# Attiny_bot.net
KiCad netlist of a schematic drawn in EAGLE
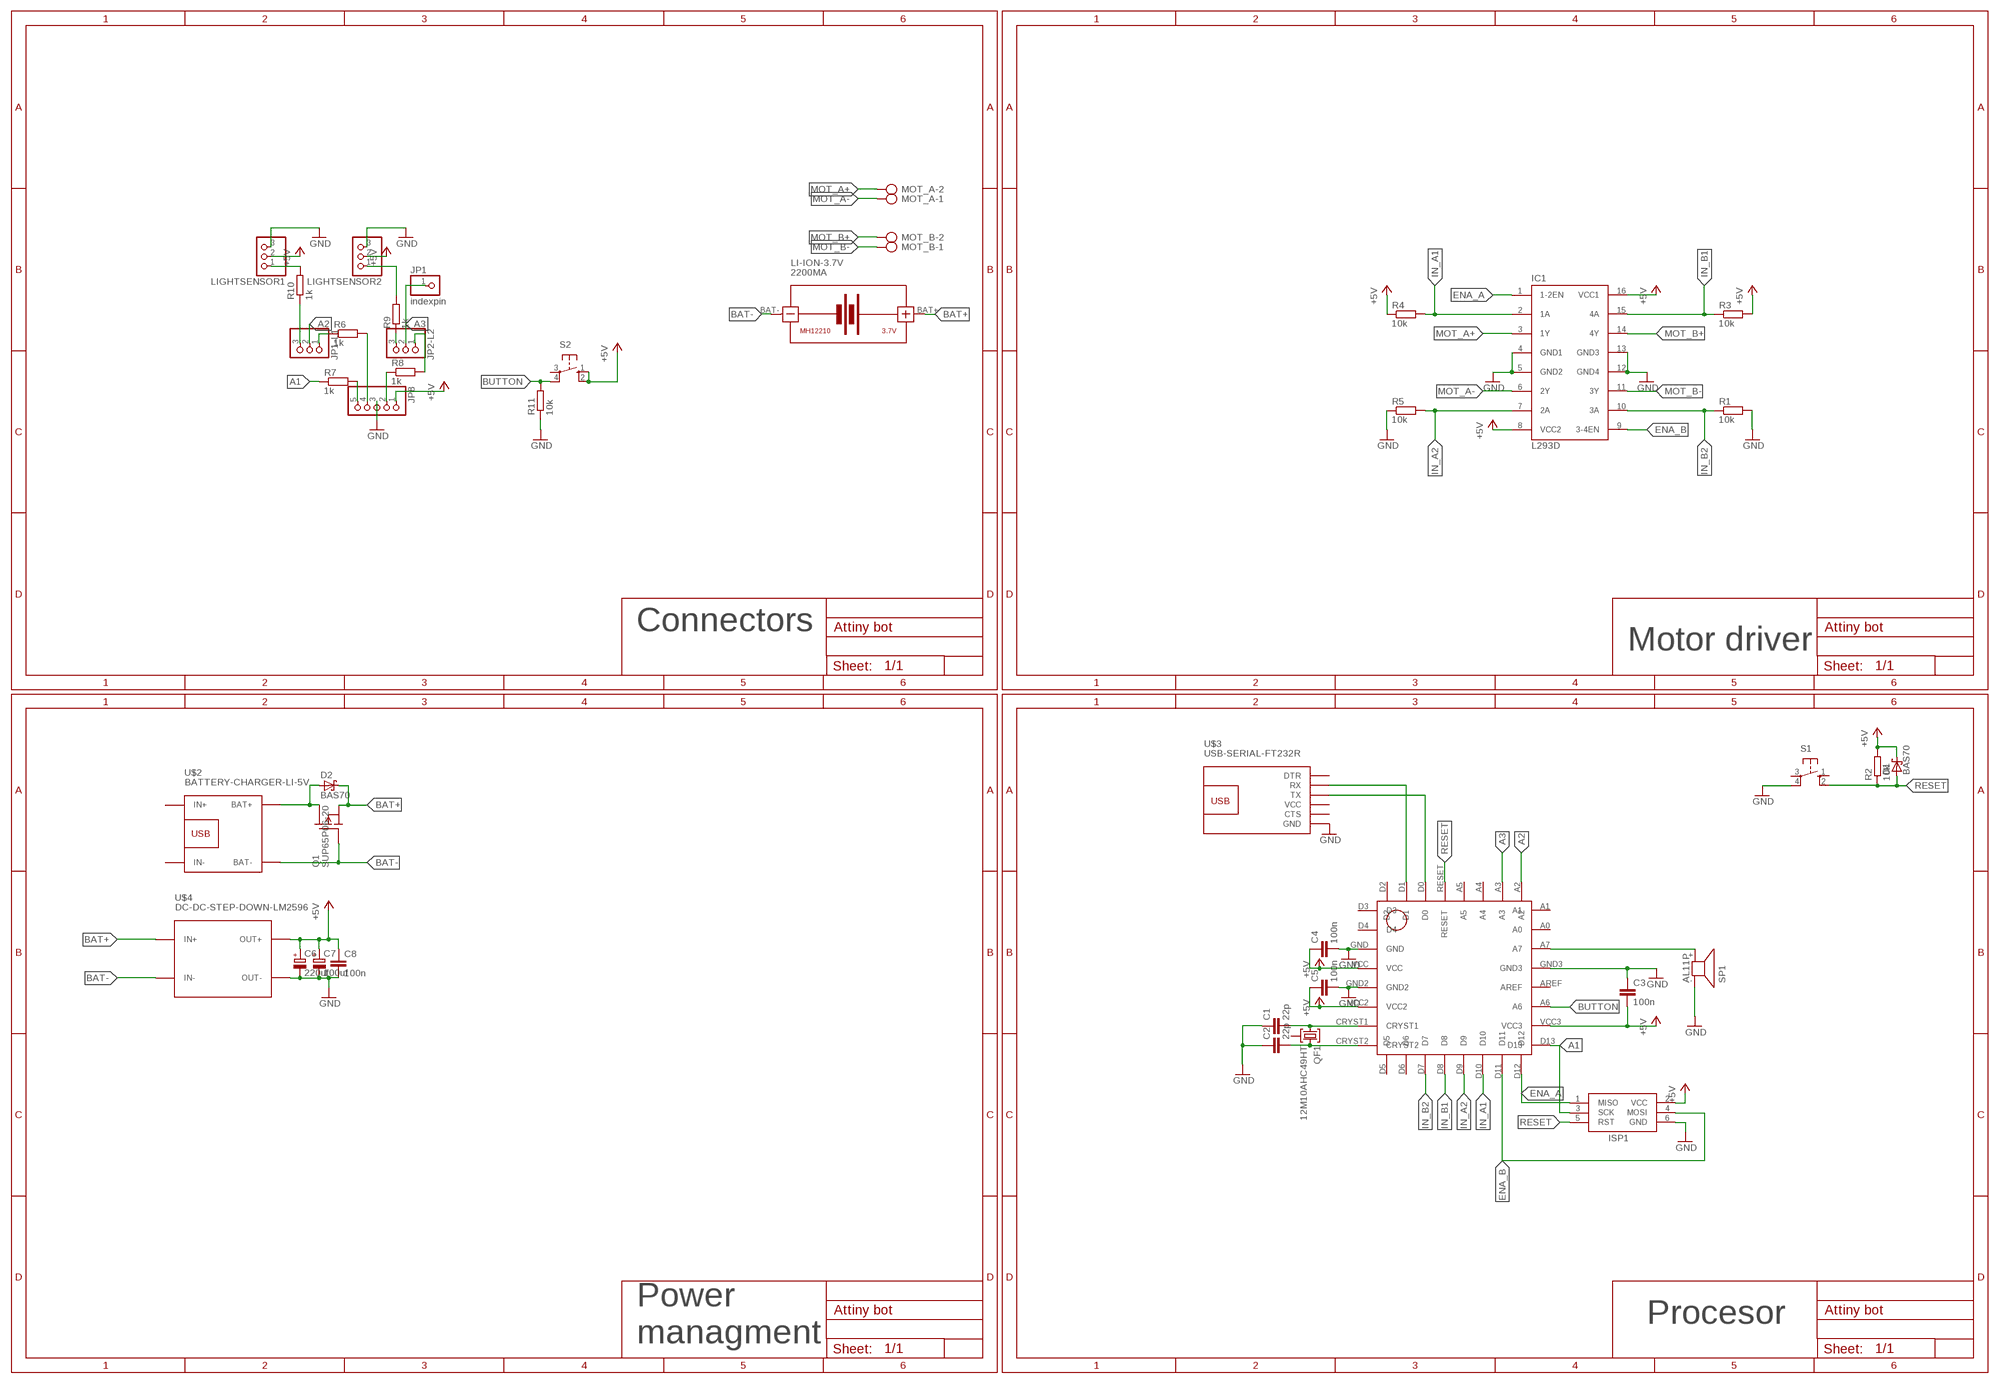
[diagram p0: schematic, sheet 1]

(export (version "E")
  (design (tool "Eeschema 10.0.6"))
  (components
    (comp (ref "C1")
      (value "22p")
      (footprint "eagle-import:C1206")
      (libsource (lib "eagle-import") (part "C-EUC1206"))
    )
    (comp (ref "C2")
      (value "22p")
      (footprint "eagle-import:C1206")
      (libsource (lib "eagle-import") (part "C-EUC1206"))
    )
    (comp (ref "C3")
      (value "100n")
      (footprint "eagle-import:C1206")
      (libsource (lib "eagle-import") (part "C-EUC1206"))
    )
    (comp (ref "C4")
      (value "100n")
      (footprint "eagle-import:C1206")
      (libsource (lib "eagle-import") (part "C-EUC1206"))
    )
    (comp (ref "C5")
      (value "100n")
      (footprint "eagle-import:C1206")
      (libsource (lib "eagle-import") (part "C-EUC1206"))
    )
    (comp (ref "C6")
      (value "220uf")
      (footprint "eagle-import:E3,5-8")
      (libsource (lib "eagle-import") (part "CPOL-EUE3.5-8"))
    )
    (comp (ref "C7")
      (value "100uf")
      (footprint "eagle-import:E3,5-8")
      (libsource (lib "eagle-import") (part "CPOL-EUE3.5-8"))
    )
    (comp (ref "C8")
      (value "100n")
      (footprint "eagle-import:C1206")
      (libsource (lib "eagle-import") (part "C-EUC1206"))
    )
    (comp (ref "D1")
      (value "BAS70")
      (footprint "eagle-import:SOT23")
      (libsource (lib "eagle-import") (part "BAS70"))
    )
    (comp (ref "D2")
      (value "BAS70")
      (footprint "eagle-import:SOT23")
      (libsource (lib "eagle-import") (part "BAS70"))
    )
    (comp (ref "IC1")
      (value "L293D")
      (footprint "eagle-import:DIL16")
      (libsource (lib "eagle-import") (part "L293D"))
    )
    (comp (ref "ISP1")
      (value "AVRISP-6")
      (footprint "eagle-import:AVRISP")
      (libsource (lib "eagle-import") (part "AVRISP-6"))
    )
    (comp (ref "JP1")
      (value "indexpin")
      (footprint "eagle-import:1X01")
      (libsource (lib "eagle-import") (part "PINHD-1X1"))
    )
    (comp (ref "JP1-L1")
      (value "PINHD-1X3")
      (footprint "eagle-import:1X03")
      (libsource (lib "eagle-import") (part "PINHD-1X3"))
    )
    (comp (ref "JP2-L2")
      (value "PINHD-1X3")
      (footprint "eagle-import:1X03")
      (libsource (lib "eagle-import") (part "PINHD-1X3"))
    )
    (comp (ref "JP8")
      (value "PINHD-1X5")
      (footprint "eagle-import:1X05")
      (libsource (lib "eagle-import") (part "PINHD-1X5"))
    )
    (comp (ref "LI-ION-3.7V")
      (value "2200MA")
      (footprint "eagle-import:BATTERY-LI-MH12210")
      (libsource (lib "eagle-import") (part "BATTERY-LI-MH12210"))
    )
    (comp (ref "LIGHTSENSOR1")
      (value "PINHD-1X3")
      (footprint "eagle-import:1X03")
      (libsource (lib "eagle-import") (part "PINHD-1X3"))
    )
    (comp (ref "LIGHTSENSOR2")
      (value "PINHD-1X3")
      (footprint "eagle-import:1X03")
      (libsource (lib "eagle-import") (part "PINHD-1X3"))
    )
    (comp (ref "MOT_A")
      (value "AK500/2")
      (footprint "eagle-import:AK500_2")
      (libsource (lib "eagle-import") (part "AK500/2"))
    )
    (comp (ref "MOT_B")
      (value "AK500/2")
      (footprint "eagle-import:AK500_2")
      (libsource (lib "eagle-import") (part "AK500/2"))
    )
    (comp (ref "Q1")
      (value "SUP65P06-20")
      (footprint "eagle-import:TO220")
      (libsource (lib "eagle-import") (part "SUP65P06-20"))
    )
    (comp (ref "QF1")
      (value "12M10AHC49HT")
      (footprint "eagle-import:HC49U")
      (libsource (lib "eagle-import") (part "12M10AHC49HT"))
    )
    (comp (ref "R1")
      (value "10k")
      (footprint "eagle-import:R1206")
      (libsource (lib "eagle-import") (part "R-EU_R1206"))
    )
    (comp (ref "R2")
      (value "10k")
      (footprint "eagle-import:R1206")
      (libsource (lib "eagle-import") (part "R-EU_R1206"))
    )
    (comp (ref "R3")
      (value "10k")
      (footprint "eagle-import:R1206")
      (libsource (lib "eagle-import") (part "R-EU_R1206"))
    )
    (comp (ref "R4")
      (value "10k")
      (footprint "eagle-import:R1206")
      (libsource (lib "eagle-import") (part "R-EU_R1206"))
    )
    (comp (ref "R5")
      (value "10k")
      (footprint "eagle-import:R1206")
      (libsource (lib "eagle-import") (part "R-EU_R1206"))
    )
    (comp (ref "R6")
      (value "1k")
      (footprint "eagle-import:R1206")
      (libsource (lib "eagle-import") (part "R-EU_R1206"))
    )
    (comp (ref "R7")
      (value "1k")
      (footprint "eagle-import:R1206")
      (libsource (lib "eagle-import") (part "R-EU_R1206"))
    )
    (comp (ref "R8")
      (value "1k")
      (footprint "eagle-import:R1206")
      (libsource (lib "eagle-import") (part "R-EU_R1206"))
    )
    (comp (ref "R9")
      (value "1k")
      (footprint "eagle-import:R1206")
      (libsource (lib "eagle-import") (part "R-EU_R1206"))
    )
    (comp (ref "R10")
      (value "1k")
      (footprint "eagle-import:R1206")
      (libsource (lib "eagle-import") (part "R-EU_R1206"))
    )
    (comp (ref "R11")
      (value "10k")
      (footprint "eagle-import:R1206")
      (libsource (lib "eagle-import") (part "R-EU_R1206"))
    )
    (comp (ref "S1")
      (value "10-XX")
      (footprint "eagle-import:B3F-10XX")
      (fields (field (name "MPN") "B3F-1000"))
      (libsource (lib "eagle-import") (part "10-XX"))
    )
    (comp (ref "S2")
      (value "10-XX")
      (footprint "eagle-import:B3F-10XX")
      (fields (field (name "MPN") "B3F-1000"))
      (libsource (lib "eagle-import") (part "10-XX"))
    )
    (comp (ref "SP1")
      (value "AL11P")
      (footprint "eagle-import:AL11P")
      (libsource (lib "eagle-import") (part "AL11P"))
    )
    (comp (ref "U$1")
      (value "PROCESSOR")
      (footprint "eagle-import:PROCESOR")
      (libsource (lib "eagle-import") (part "PROCESSOR"))
    )
    (comp (ref "U$2")
      (value "BATTERY-CHARGER-LI-5V")
      (footprint "eagle-import:BATTERY-CHARGER-LI-5V")
      (libsource (lib "eagle-import") (part "BATTERY-CHARGER-LI-5V"))
    )
    (comp (ref "U$3")
      (value "USB-SERIAL-FT232R")
      (footprint "eagle-import:USB-SERIAL-FT232R")
      (libsource (lib "eagle-import") (part "USB-SERIAL-FT232R"))
    )
    (comp (ref "U$4")
      (value "DC-DC-STEP-DOWN-LM2596")
      (footprint "eagle-import:DC-DC-STEP-DOWN-LM2596")
      (libsource (lib "eagle-import") (part "DC-DC-STEP-DOWN-LM2596"))
    )
  )
  (nets
    (net (code "1") (name "+5V") (class "Default")
      (node (ref "C3") (pin "2") (pinfunction "2_2") (pintype "passive"))
      (node (ref "C4") (pin "1") (pinfunction "1_1") (pintype "passive"))
      (node (ref "C5") (pin "1") (pinfunction "1_1") (pintype "passive"))
      (node (ref "C6") (pin "+") (pinfunction "+_+") (pintype "passive"))
      (node (ref "C7") (pin "+") (pinfunction "+_+") (pintype "passive"))
      (node (ref "C8") (pin "1") (pinfunction "1_1") (pintype "passive"))
      (node (ref "D1") (pin "3") (pinfunction "C_3") (pintype "passive"))
      (node (ref "IC1") (pin "16") (pinfunction "VCC1_16") (pintype "power_in"))
      (node (ref "IC1") (pin "8") (pinfunction "VCC2_8") (pintype "power_in"))
      (node (ref "ISP1") (pin "2") (pinfunction "VCC_2") (pintype "power_in"))
      (node (ref "JP8") (pin "1") (pinfunction "1_1") (pintype "passive"))
      (node (ref "LIGHTSENSOR1") (pin "2") (pinfunction "2_2") (pintype "passive"))
      (node (ref "LIGHTSENSOR2") (pin "2") (pinfunction "2_2") (pintype "passive"))
      (node (ref "R2") (pin "2") (pinfunction "2_2") (pintype "passive"))
      (node (ref "R3") (pin "2") (pinfunction "2_2") (pintype "passive"))
      (node (ref "R4") (pin "1") (pinfunction "1_1") (pintype "passive"))
      (node (ref "S2") (pin "1") (pinfunction "S_1") (pintype "passive"))
      (node (ref "S2") (pin "2") (pinfunction "S1_2") (pintype "passive"))
      (node (ref "U$1") (pin "VCC") (pinfunction "VCC_VCC") (pintype "bidirectional"))
      (node (ref "U$1") (pin "VCC2") (pinfunction "VCC2_VCC2") (pintype "bidirectional"))
      (node (ref "U$1") (pin "VCC3") (pinfunction "VCC3_VCC3") (pintype "bidirectional"))
      (node (ref "U$4") (pin "OUT+") (pinfunction "OUT+_OUT+") (pintype "bidirectional"))
    )
    (net (code "2") (name "/VCC") (class "Default")
      (node (ref "U$3") (pin "4") (pinfunction "VCC_4") (pintype "power_in"))
    )
    (net (code "3") (name "A1") (class "Default")
      (node (ref "ISP1") (pin "3") (pinfunction "SCK_3") (pintype "output"))
      (node (ref "R7") (pin "1") (pinfunction "1_1") (pintype "passive"))
      (node (ref "U$1") (pin "D13") (pinfunction "D13_D13") (pintype "bidirectional"))
    )
    (net (code "4") (name "A2") (class "Default")
      (node (ref "JP1-L1") (pin "2") (pinfunction "2_2") (pintype "passive"))
      (node (ref "U$1") (pin "A2") (pinfunction "A2_A2") (pintype "bidirectional"))
    )
    (net (code "5") (name "A3") (class "Default")
      (node (ref "JP1") (pin "1") (pinfunction "1_1") (pintype "passive"))
      (node (ref "JP2-L2") (pin "2") (pinfunction "2_2") (pintype "passive"))
      (node (ref "U$1") (pin "A3") (pinfunction "A3_A3") (pintype "bidirectional"))
    )
    (net (code "6") (name "BAT+") (class "Default")
      (node (ref "D2") (pin "3") (pinfunction "C_3") (pintype "passive"))
      (node (ref "LI-ION-3.7V") (pin "BAT+") (pinfunction "BAT+_BAT+") (pintype "power_in"))
      (node (ref "Q1") (pin "3") (pinfunction "S_3") (pintype "passive"))
      (node (ref "U$4") (pin "IN+") (pinfunction "IN+_IN+") (pintype "bidirectional"))
    )
    (net (code "7") (name "BAT-") (class "Default")
      (node (ref "LI-ION-3.7V") (pin "BAT-") (pinfunction "BAT-_BAT-") (pintype "power_in"))
      (node (ref "Q1") (pin "1") (pinfunction "G_1") (pintype "passive"))
      (node (ref "U$2") (pin "BAT-") (pinfunction "BAT-_BAT-") (pintype "bidirectional"))
      (node (ref "U$4") (pin "IN-") (pinfunction "IN-_IN-") (pintype "bidirectional"))
    )
    (net (code "8") (name "BUTTON") (class "Default")
      (node (ref "R11") (pin "2") (pinfunction "2_2") (pintype "passive"))
      (node (ref "S2") (pin "4") (pinfunction "P1_4") (pintype "passive"))
      (node (ref "U$1") (pin "A6") (pinfunction "A6_A6") (pintype "bidirectional"))
    )
    (net (code "9") (name "ENA_A") (class "Default")
      (node (ref "IC1") (pin "1") (pinfunction "1-2EN_1") (pintype "input"))
      (node (ref "ISP1") (pin "1") (pinfunction "MISO_1") (pintype "input"))
      (node (ref "U$1") (pin "D12") (pinfunction "D12_D12") (pintype "bidirectional"))
    )
    (net (code "10") (name "ENA_B") (class "Default")
      (node (ref "IC1") (pin "9") (pinfunction "3-4EN_9") (pintype "input"))
      (node (ref "ISP1") (pin "4") (pinfunction "MOSI_4") (pintype "output"))
      (node (ref "U$1") (pin "D11") (pinfunction "D11_D11") (pintype "bidirectional"))
    )
    (net (code "11") (name "GND") (class "Default")
      (node (ref "C1") (pin "1") (pinfunction "1_1") (pintype "passive"))
      (node (ref "C2") (pin "1") (pinfunction "1_1") (pintype "passive"))
      (node (ref "C3") (pin "1") (pinfunction "1_1") (pintype "passive"))
      (node (ref "C4") (pin "2") (pinfunction "2_2") (pintype "passive"))
      (node (ref "C5") (pin "2") (pinfunction "2_2") (pintype "passive"))
      (node (ref "C6") (pin "-") (pinfunction "-_-") (pintype "passive"))
      (node (ref "C7") (pin "-") (pinfunction "-_-") (pintype "passive"))
      (node (ref "C8") (pin "2") (pinfunction "2_2") (pintype "passive"))
      (node (ref "IC1") (pin "12") (pinfunction "GND4_12") (pintype "power_in"))
      (node (ref "IC1") (pin "13") (pinfunction "GND3_13") (pintype "power_in"))
      (node (ref "IC1") (pin "4") (pinfunction "GND1_4") (pintype "power_in"))
      (node (ref "IC1") (pin "5") (pinfunction "GND2_5") (pintype "power_in"))
      (node (ref "ISP1") (pin "6") (pinfunction "GND_6") (pintype "power_in"))
      (node (ref "JP8") (pin "3") (pinfunction "3_3") (pintype "passive"))
      (node (ref "LIGHTSENSOR1") (pin "3") (pinfunction "3_3") (pintype "passive"))
      (node (ref "LIGHTSENSOR2") (pin "3") (pinfunction "3_3") (pintype "passive"))
      (node (ref "R1") (pin "2") (pinfunction "2_2") (pintype "passive"))
      (node (ref "R11") (pin "1") (pinfunction "1_1") (pintype "passive"))
      (node (ref "R5") (pin "1") (pinfunction "1_1") (pintype "passive"))
      (node (ref "S1") (pin "4") (pinfunction "P1_4") (pintype "passive"))
      (node (ref "SP1") (pin "-") (pinfunction "1_-") (pintype "passive"))
      (node (ref "U$1") (pin "GND") (pinfunction "GND_GND") (pintype "bidirectional"))
      (node (ref "U$1") (pin "GND2") (pinfunction "GND2_GND2") (pintype "bidirectional"))
      (node (ref "U$1") (pin "GND3") (pinfunction "GND3_GND3") (pintype "bidirectional"))
      (node (ref "U$3") (pin "6") (pinfunction "GND_6") (pintype "bidirectional"))
      (node (ref "U$4") (pin "OUT-") (pinfunction "OUT-_OUT-") (pintype "bidirectional"))
    )
    (net (code "12") (name "IN_A1") (class "Default")
      (node (ref "IC1") (pin "2") (pinfunction "1A_2") (pintype "input"))
      (node (ref "R4") (pin "2") (pinfunction "2_2") (pintype "passive"))
      (node (ref "U$1") (pin "D10") (pinfunction "D10_D10") (pintype "bidirectional"))
    )
    (net (code "13") (name "IN_A2") (class "Default")
      (node (ref "IC1") (pin "7") (pinfunction "2A_7") (pintype "input"))
      (node (ref "R5") (pin "2") (pinfunction "2_2") (pintype "passive"))
      (node (ref "U$1") (pin "D9") (pinfunction "D9_D9") (pintype "bidirectional"))
    )
    (net (code "14") (name "IN_B1") (class "Default")
      (node (ref "IC1") (pin "15") (pinfunction "4A_15") (pintype "input"))
      (node (ref "R3") (pin "1") (pinfunction "1_1") (pintype "passive"))
      (node (ref "U$1") (pin "D8") (pinfunction "D8_D8") (pintype "bidirectional"))
    )
    (net (code "15") (name "IN_B2") (class "Default")
      (node (ref "IC1") (pin "10") (pinfunction "3A_10") (pintype "input"))
      (node (ref "R1") (pin "1") (pinfunction "1_1") (pintype "passive"))
      (node (ref "U$1") (pin "D7") (pinfunction "D7_D7") (pintype "bidirectional"))
    )
    (net (code "16") (name "MOT_A+") (class "Default")
      (node (ref "IC1") (pin "3") (pinfunction "1Y_3") (pintype "output"))
      (node (ref "MOT_A") (pin "2") (pinfunction "KL_2") (pintype "passive"))
    )
    (net (code "17") (name "MOT_A-") (class "Default")
      (node (ref "IC1") (pin "6") (pinfunction "2Y_6") (pintype "output"))
      (node (ref "MOT_A") (pin "1") (pinfunction "KL_1") (pintype "passive"))
    )
    (net (code "18") (name "MOT_B+") (class "Default")
      (node (ref "IC1") (pin "14") (pinfunction "4Y_14") (pintype "output"))
      (node (ref "MOT_B") (pin "2") (pinfunction "KL_2") (pintype "passive"))
    )
    (net (code "19") (name "MOT_B-") (class "Default")
      (node (ref "IC1") (pin "11") (pinfunction "3Y_11") (pintype "output"))
      (node (ref "MOT_B") (pin "1") (pinfunction "KL_1") (pintype "passive"))
    )
    (net (code "20") (name "Net-(C1-Pad2)") (class "Default")
      (node (ref "C1") (pin "2") (pinfunction "2_2") (pintype "passive"))
      (node (ref "QF1") (pin "1") (pinfunction "1_1") (pintype "passive"))
      (node (ref "U$1") (pin "CRYST1") (pinfunction "CRYST1_CRYST1") (pintype "bidirectional"))
    )
    (net (code "21") (name "Net-(C2-Pad2)") (class "Default")
      (node (ref "C2") (pin "2") (pinfunction "2_2") (pintype "passive"))
      (node (ref "QF1") (pin "3") (pinfunction "3_3") (pintype "passive"))
      (node (ref "U$1") (pin "CRYST2") (pinfunction "CRYST2_CRYST2") (pintype "bidirectional"))
    )
    (net (code "22") (name "Net-(D2-A)") (class "Default")
      (node (ref "D2") (pin "1") (pinfunction "A_1") (pintype "passive"))
      (node (ref "Q1") (pin "2") (pinfunction "D_2") (pintype "passive"))
      (node (ref "U$2") (pin "BAT+") (pinfunction "BAT+_BAT+") (pintype "bidirectional"))
    )
    (net (code "23") (name "Net-(JP1-L1-Pad1)") (class "Default")
      (node (ref "JP1-L1") (pin "1") (pinfunction "1_1") (pintype "passive"))
      (node (ref "R6") (pin "1") (pinfunction "1_1") (pintype "passive"))
    )
    (net (code "24") (name "Net-(JP1-L1-Pad3)") (class "Default")
      (node (ref "JP1-L1") (pin "3") (pinfunction "3_3") (pintype "passive"))
      (node (ref "R10") (pin "1") (pinfunction "1_1") (pintype "passive"))
    )
    (net (code "25") (name "Net-(JP2-L2-Pad1)") (class "Default")
      (node (ref "JP2-L2") (pin "1") (pinfunction "1_1") (pintype "passive"))
      (node (ref "R8") (pin "2") (pinfunction "2_2") (pintype "passive"))
    )
    (net (code "26") (name "Net-(JP2-L2-Pad3)") (class "Default")
      (node (ref "JP2-L2") (pin "3") (pinfunction "3_3") (pintype "passive"))
      (node (ref "R9") (pin "1") (pinfunction "1_1") (pintype "passive"))
    )
    (net (code "27") (name "Net-(JP8-Pad2)") (class "Default")
      (node (ref "JP8") (pin "2") (pinfunction "2_2") (pintype "passive"))
      (node (ref "R8") (pin "1") (pinfunction "1_1") (pintype "passive"))
    )
    (net (code "28") (name "Net-(JP8-Pad4)") (class "Default")
      (node (ref "JP8") (pin "4") (pinfunction "4_4") (pintype "passive"))
      (node (ref "R6") (pin "2") (pinfunction "2_2") (pintype "passive"))
    )
    (net (code "29") (name "Net-(JP8-Pad5)") (class "Default")
      (node (ref "JP8") (pin "5") (pinfunction "5_5") (pintype "passive"))
      (node (ref "R7") (pin "2") (pinfunction "2_2") (pintype "passive"))
    )
    (net (code "30") (name "Net-(LIGHTSENSOR1-Pad1)") (class "Default")
      (node (ref "LIGHTSENSOR1") (pin "1") (pinfunction "1_1") (pintype "passive"))
      (node (ref "R10") (pin "2") (pinfunction "2_2") (pintype "passive"))
    )
    (net (code "31") (name "Net-(LIGHTSENSOR2-Pad1)") (class "Default")
      (node (ref "LIGHTSENSOR2") (pin "1") (pinfunction "1_1") (pintype "passive"))
      (node (ref "R9") (pin "2") (pinfunction "2_2") (pintype "passive"))
    )
    (net (code "32") (name "Net-(SP1-2)") (class "Default")
      (node (ref "SP1") (pin "+") (pinfunction "2_+") (pintype "passive"))
      (node (ref "U$1") (pin "A7") (pinfunction "A7_A7") (pintype "bidirectional"))
    )
    (net (code "33") (name "Net-(U$3-RX)") (class "Default")
      (node (ref "U$1") (pin "D1") (pinfunction "D1_D1") (pintype "bidirectional"))
      (node (ref "U$3") (pin "2") (pinfunction "RX_2") (pintype "bidirectional"))
    )
    (net (code "34") (name "Net-(U$3-TX)") (class "Default")
      (node (ref "U$1") (pin "D0") (pinfunction "D0_D0") (pintype "bidirectional"))
      (node (ref "U$3") (pin "3") (pinfunction "TX_3") (pintype "bidirectional"))
    )
    (net (code "35") (name "RESET") (class "Default")
      (node (ref "D1") (pin "1") (pinfunction "A_1") (pintype "passive"))
      (node (ref "ISP1") (pin "5") (pinfunction "RST_5") (pintype "output"))
      (node (ref "R2") (pin "1") (pinfunction "1_1") (pintype "passive"))
      (node (ref "S1") (pin "2") (pinfunction "S1_2") (pintype "passive"))
      (node (ref "U$1") (pin "RESET") (pinfunction "RESET_RESET") (pintype "bidirectional"))
    )
    (net (code "36") (name "unconnected-(QF1-Pad2)") (class "Default")
      (node (ref "QF1") (pin "2") (pinfunction "2_2") (pintype "passive"))
    )
    (net (code "37") (name "unconnected-(S1-P-Pad3)") (class "Default")
      (node (ref "S1") (pin "3") (pinfunction "P_3") (pintype "passive"))
    )
    (net (code "38") (name "unconnected-(S1-S-Pad1)") (class "Default")
      (node (ref "S1") (pin "1") (pinfunction "S_1") (pintype "passive"))
    )
    (net (code "39") (name "unconnected-(S2-P-Pad3)") (class "Default")
      (node (ref "S2") (pin "3") (pinfunction "P_3") (pintype "passive"))
    )
    (net (code "40") (name "unconnected-(U$1-PadA0)") (class "Default")
      (node (ref "U$1") (pin "A0") (pinfunction "A0_A0") (pintype "bidirectional"))
    )
    (net (code "41") (name "unconnected-(U$1-PadA1)") (class "Default")
      (node (ref "U$1") (pin "A1") (pinfunction "A1_A1") (pintype "bidirectional"))
    )
    (net (code "42") (name "unconnected-(U$1-PadA4)") (class "Default")
      (node (ref "U$1") (pin "A4") (pinfunction "A4_A4") (pintype "bidirectional"))
    )
    (net (code "43") (name "unconnected-(U$1-PadA5)") (class "Default")
      (node (ref "U$1") (pin "A5") (pinfunction "A5_A5") (pintype "bidirectional"))
    )
    (net (code "44") (name "unconnected-(U$1-PadAREF)") (class "Default")
      (node (ref "U$1") (pin "AREF") (pinfunction "AREF_AREF") (pintype "bidirectional"))
    )
    (net (code "45") (name "unconnected-(U$1-PadD2)") (class "Default")
      (node (ref "U$1") (pin "D2") (pinfunction "D2_D2") (pintype "bidirectional"))
    )
    (net (code "46") (name "unconnected-(U$1-PadD3)") (class "Default")
      (node (ref "U$1") (pin "D3") (pinfunction "D3_D3") (pintype "bidirectional"))
    )
    (net (code "47") (name "unconnected-(U$1-PadD4)") (class "Default")
      (node (ref "U$1") (pin "D4") (pinfunction "D4_D4") (pintype "bidirectional"))
    )
    (net (code "48") (name "unconnected-(U$1-PadD5)") (class "Default")
      (node (ref "U$1") (pin "D5") (pinfunction "D5_D5") (pintype "bidirectional"))
    )
    (net (code "49") (name "unconnected-(U$1-PadD6)") (class "Default")
      (node (ref "U$1") (pin "D6") (pinfunction "D6_D6") (pintype "bidirectional"))
    )
    (net (code "50") (name "unconnected-(U$2-PadIN+)") (class "Default")
      (node (ref "U$2") (pin "IN+") (pinfunction "IN+_IN+") (pintype "bidirectional"))
    )
    (net (code "51") (name "unconnected-(U$2-PadIN-)") (class "Default")
      (node (ref "U$2") (pin "IN-") (pinfunction "IN-_IN-") (pintype "bidirectional"))
    )
    (net (code "52") (name "unconnected-(U$3-CTS-Pad5)") (class "Default")
      (node (ref "U$3") (pin "5") (pinfunction "CTS_5") (pintype "bidirectional"))
    )
    (net (code "53") (name "unconnected-(U$3-DTR-Pad1)") (class "Default")
      (node (ref "U$3") (pin "1") (pinfunction "DTR_1") (pintype "bidirectional"))
    )
  )
)
